# 2_MCU_schdoc.net
KiCad netlist of a schematic drawn in Altium Designer
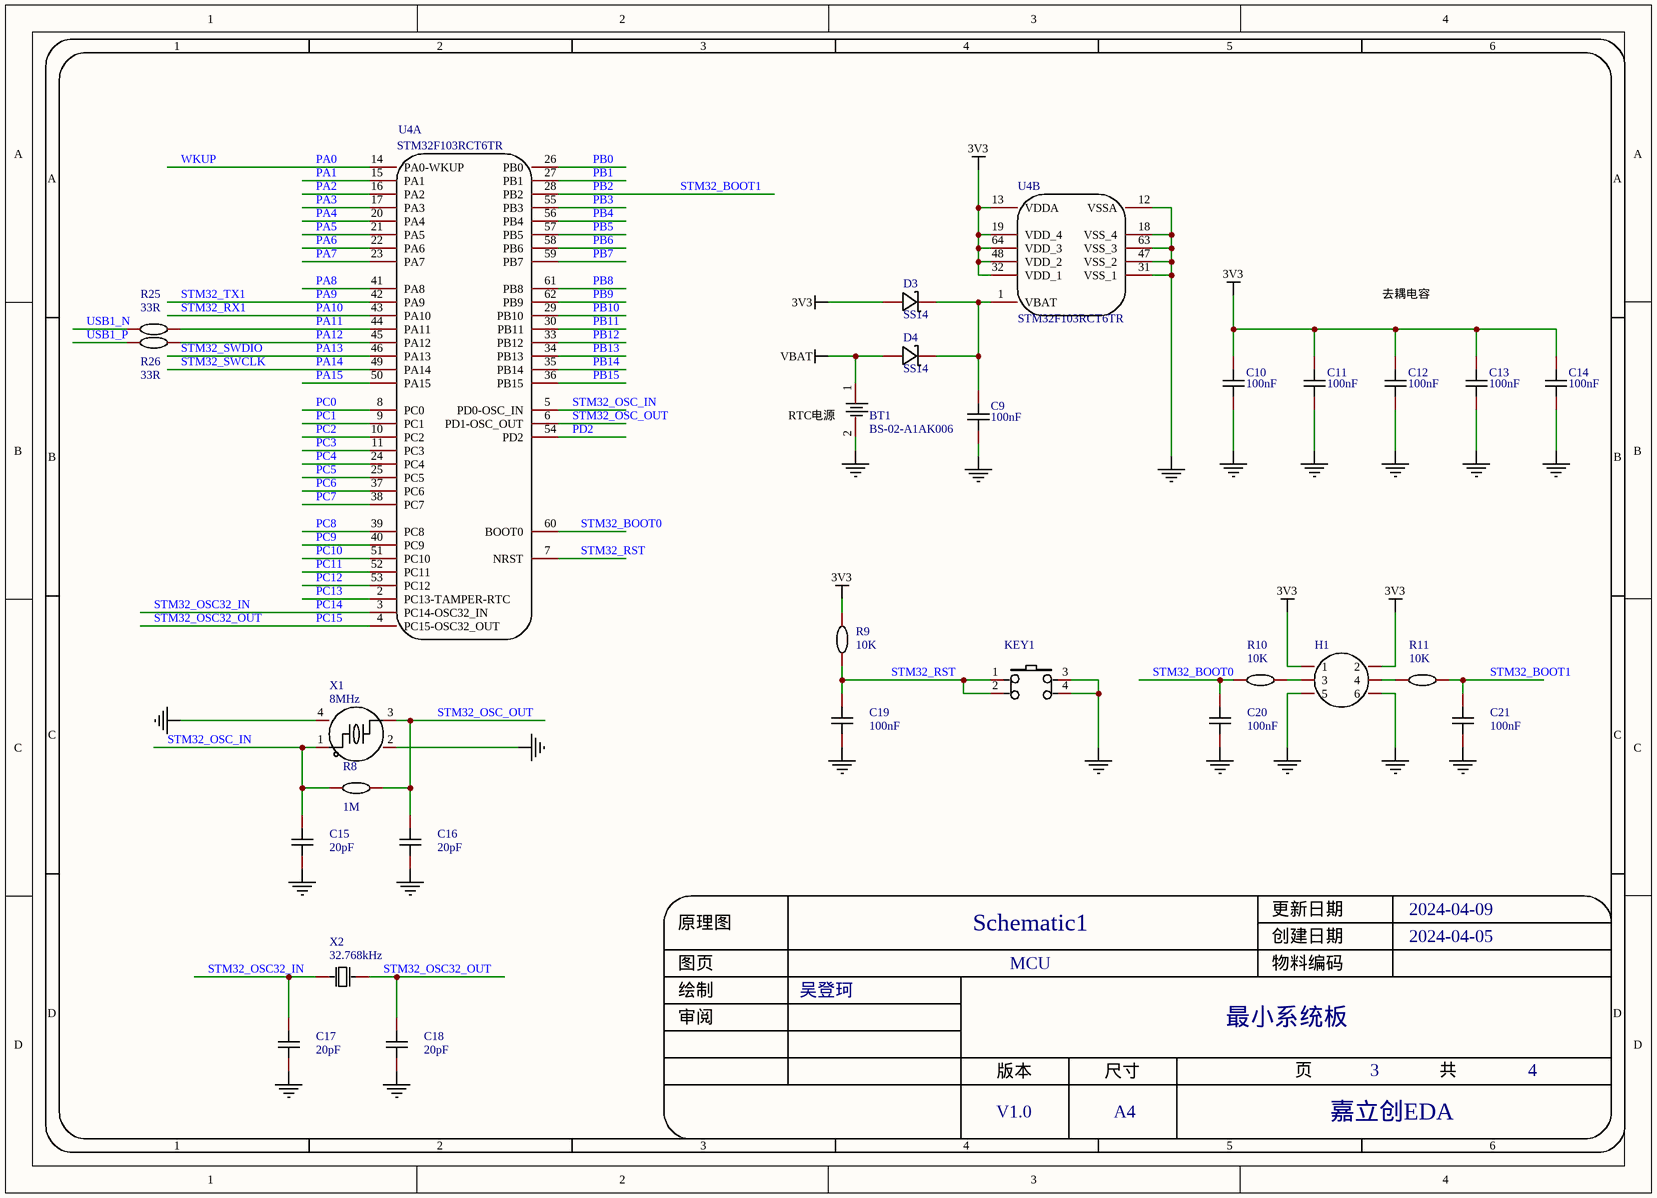
[diagram p0: 2_MCU.schdoc.schdoc]

(export (version "E")
  (design (tool "Eeschema 10.0.6"))
  (components
    (comp (ref "BT1")
      (value "BS-02-A1AK006")
      (footprint "BAT-TH_BS-02-A1AK006")
      (fields (field (name "NAME") "BS-02-A1AK006") (field (name "MANUFACTURER") "MYOUNG(美阳)"))
      (libsource (lib "altium-import") (part "root_3_BS-02-A1AK006_"))
    )
    (comp (ref "C9")
      (value "100nF")
      (footprint "C0603")
      (fields (field (name "NAME") "100nF"))
      (libsource (lib "altium-import") (part "root_1_CAP_0603_"))
    )
    (comp (ref "C10")
      (value "100nF")
      (footprint "C0603")
      (fields (field (name "NAME") "100nF"))
      (libsource (lib "altium-import") (part "root_1_CAP_0603_"))
    )
    (comp (ref "C11")
      (value "100nF")
      (footprint "C0603")
      (fields (field (name "NAME") "100nF"))
      (libsource (lib "altium-import") (part "root_1_CAP_0603_"))
    )
    (comp (ref "C12")
      (value "100nF")
      (footprint "C0603")
      (fields (field (name "NAME") "100nF"))
      (libsource (lib "altium-import") (part "root_1_CAP_0603_"))
    )
    (comp (ref "C13")
      (value "100nF")
      (footprint "C0603")
      (fields (field (name "NAME") "100nF"))
      (libsource (lib "altium-import") (part "root_1_CAP_0603_"))
    )
    (comp (ref "C14")
      (value "100nF")
      (footprint "C0603")
      (fields (field (name "NAME") "100nF"))
      (libsource (lib "altium-import") (part "root_1_CAP_0603_"))
    )
    (comp (ref "C15")
      (value "20pF")
      (footprint "C0603")
      (fields (field (name "NAME") "20pF"))
      (libsource (lib "altium-import") (part "root_1_CAP_0603_"))
    )
    (comp (ref "C16")
      (value "20pF")
      (footprint "C0603")
      (fields (field (name "NAME") "20pF"))
      (libsource (lib "altium-import") (part "root_1_CAP_0603_"))
    )
    (comp (ref "C17")
      (value "20pF")
      (footprint "C0603")
      (fields (field (name "NAME") "20pF"))
      (libsource (lib "altium-import") (part "root_1_CAP_0603_"))
    )
    (comp (ref "C18")
      (value "20pF")
      (footprint "C0603")
      (fields (field (name "NAME") "20pF"))
      (libsource (lib "altium-import") (part "root_1_CAP_0603_"))
    )
    (comp (ref "C19")
      (value "100nF")
      (footprint "C0603")
      (fields (field (name "NAME") "100nF"))
      (libsource (lib "altium-import") (part "root_1_CAP_0603_"))
    )
    (comp (ref "C20")
      (value "100nF")
      (footprint "C0603")
      (fields (field (name "NAME") "100nF"))
      (libsource (lib "altium-import") (part "root_1_CAP_0603_"))
    )
    (comp (ref "C21")
      (value "100nF")
      (footprint "C0603")
      (fields (field (name "NAME") "100nF"))
      (libsource (lib "altium-import") (part "root_1_CAP_0603_"))
    )
    (comp (ref "D3")
      (value "SS14")
      (footprint "SMA_L4.3-W2.6-LS5.2-RD")
      (fields (field (name "NAME") "SS14") (field (name "MANUFACTURER") "onsemi(安森美)"))
      (libsource (lib "altium-import") (part "root_2_SS14_C83852_"))
    )
    (comp (ref "D4")
      (value "SS14")
      (footprint "SMA_L4.3-W2.6-LS5.2-RD")
      (fields (field (name "NAME") "SS14") (field (name "MANUFACTURER") "onsemi(安森美)"))
      (libsource (lib "altium-import") (part "root_2_SS14_C83852_"))
    )
    (comp (ref "H1")
      (value "HDR-F_2.54_2x3")
      (footprint "HDR-TH_6P-P2.54-V-F-R2-C3-S2.54")
      (libsource (lib "altium-import") (part "root_0_HDR-F_2.54_2x3_"))
    )
    (comp (ref "KEY1")
      (value "6x6x6塑料头")
      (footprint "SW-SMD_4P-L6.0-W6.0-P4.50-LS8.6")
      (fields (field (name "MANUFACTURER") "国产"))
      (libsource (lib "altium-import") (part "root_0_6x6x6塑料头_"))
    )
    (comp (ref "R8")
      (value "1M")
      (footprint "R0603")
      (fields (field (name "NAME") "1M"))
      (libsource (lib "altium-import") (part "root_0_Res_0603_"))
    )
    (comp (ref "R9")
      (value "10K")
      (footprint "R0603")
      (fields (field (name "NAME") "10K"))
      (libsource (lib "altium-import") (part "root_1_Res_0603_"))
    )
    (comp (ref "R10")
      (value "10K")
      (footprint "R0603")
      (fields (field (name "NAME") "10K"))
      (libsource (lib "altium-import") (part "root_0_Res_0603_"))
    )
    (comp (ref "R11")
      (value "10K")
      (footprint "R0603")
      (fields (field (name "NAME") "10K"))
      (libsource (lib "altium-import") (part "root_0_Res_0603_"))
    )
    (comp (ref "R25")
      (value "33R")
      (footprint "R0603")
      (fields (field (name "NAME") "33R"))
      (libsource (lib "altium-import") (part "root_0_Res_0603_"))
    )
    (comp (ref "R26")
      (value "33R")
      (footprint "R0603")
      (fields (field (name "NAME") "33R"))
      (libsource (lib "altium-import") (part "root_0_Res_0603_"))
    )
    (comp (ref "U4")
      (value "STM32F103RCT6TR")
      (footprint "LQFP-64_L10.0-W10.0-P0.50-LS12.0-BL")
      (fields (field (name "NAME") "STM32F103RCT6TR") (field (name "MANUFACTURER") "ST(意法半导体)"))
      (libsource (lib "altium-import") (part "root_0_STM32F103RCT6TR_"))
    )
    (comp (ref "X1")
      (value "8MHz")
      (footprint "OSC-SMD_4P-L3.2-W2.5-BL")
      (fields
        (field (name "NAME") "8MHz")
        (field (name "MANUFACTURER") "YXC(扬兴晶振)")
        (field (name "MANUFACTURER PART") "X32258MOB4SI")
      )
      (libsource (lib "altium-import") (part "root_0_X32258MOB4SI_"))
    )
    (comp (ref "X2")
      (value "32.768kHz")
      (footprint "OSC-SMD_L3.2-W1.5")
      (fields
        (field (name "NAME") "32.768kHz")
        (field (name "MANUFACTURER") "KDS(大真空)")
        (field (name "MANUFACTURER PART") "DST310S 32.768KHz")
      )
      (libsource (lib "altium-import") (part "root_0_DST310S 32.768KHz_"))
    )
  )
  (nets
    (net (code "1") (name "/PA0") (class "Default")
      (node (ref "U4") (pin "14") (pinfunction "PA0-WKUP_14") (pintype "passive"))
    )
    (net (code "2") (name "/PA1") (class "Default")
      (node (ref "U4") (pin "15") (pinfunction "PA1_15") (pintype "passive"))
    )
    (net (code "3") (name "/PA2") (class "Default")
      (node (ref "U4") (pin "16") (pinfunction "PA2_16") (pintype "passive"))
    )
    (net (code "4") (name "/PA3") (class "Default")
      (node (ref "U4") (pin "17") (pinfunction "PA3_17") (pintype "passive"))
    )
    (net (code "5") (name "/PA4") (class "Default")
      (node (ref "U4") (pin "20") (pinfunction "PA4_20") (pintype "passive"))
    )
    (net (code "6") (name "/PA5") (class "Default")
      (node (ref "U4") (pin "21") (pinfunction "PA5_21") (pintype "passive"))
    )
    (net (code "7") (name "/PA6") (class "Default")
      (node (ref "U4") (pin "22") (pinfunction "PA6_22") (pintype "passive"))
    )
    (net (code "8") (name "/PA7") (class "Default")
      (node (ref "U4") (pin "23") (pinfunction "PA7_23") (pintype "passive"))
    )
    (net (code "9") (name "/PA8") (class "Default")
      (node (ref "U4") (pin "41") (pinfunction "PA8_41") (pintype "passive"))
    )
    (net (code "10") (name "/PA9") (class "Default")
      (node (ref "U4") (pin "42") (pinfunction "PA9_42") (pintype "passive"))
    )
    (net (code "11") (name "/PA10") (class "Default")
      (node (ref "U4") (pin "43") (pinfunction "PA10_43") (pintype "passive"))
    )
    (net (code "12") (name "/PA11") (class "Default")
      (node (ref "R25") (pin "2") (pinfunction "2_2") (pintype "passive"))
      (node (ref "U4") (pin "44") (pinfunction "PA11_44") (pintype "passive"))
    )
    (net (code "13") (name "/PA12") (class "Default")
      (node (ref "R26") (pin "2") (pinfunction "2_2") (pintype "passive"))
      (node (ref "U4") (pin "45") (pinfunction "PA12_45") (pintype "passive"))
    )
    (net (code "14") (name "/PA13") (class "Default")
      (node (ref "U4") (pin "46") (pinfunction "PA13_46") (pintype "passive"))
    )
    (net (code "15") (name "/PA14") (class "Default")
      (node (ref "U4") (pin "49") (pinfunction "PA14_49") (pintype "passive"))
    )
    (net (code "16") (name "/PA15") (class "Default")
      (node (ref "U4") (pin "50") (pinfunction "PA15_50") (pintype "passive"))
    )
    (net (code "17") (name "/PB0") (class "Default")
      (node (ref "U4") (pin "26") (pinfunction "PB0_26") (pintype "passive"))
    )
    (net (code "18") (name "/PB1") (class "Default")
      (node (ref "U4") (pin "27") (pinfunction "PB1_27") (pintype "passive"))
    )
    (net (code "19") (name "/PB2") (class "Default")
      (node (ref "C21") (pin "2") (pinfunction "2_2") (pintype "passive"))
      (node (ref "R11") (pin "2") (pinfunction "2_2") (pintype "passive"))
      (node (ref "U4") (pin "28") (pinfunction "PB2_28") (pintype "passive"))
    )
    (net (code "20") (name "/PB3") (class "Default")
      (node (ref "U4") (pin "55") (pinfunction "PB3_55") (pintype "passive"))
    )
    (net (code "21") (name "/PB4") (class "Default")
      (node (ref "U4") (pin "56") (pinfunction "PB4_56") (pintype "passive"))
    )
    (net (code "22") (name "/PB5") (class "Default")
      (node (ref "U4") (pin "57") (pinfunction "PB5_57") (pintype "passive"))
    )
    (net (code "23") (name "/PB6") (class "Default")
      (node (ref "U4") (pin "58") (pinfunction "PB6_58") (pintype "passive"))
    )
    (net (code "24") (name "/PB7") (class "Default")
      (node (ref "U4") (pin "59") (pinfunction "PB7_59") (pintype "passive"))
    )
    (net (code "25") (name "/PB8") (class "Default")
      (node (ref "U4") (pin "61") (pinfunction "PB8_61") (pintype "passive"))
    )
    (net (code "26") (name "/PB9") (class "Default")
      (node (ref "U4") (pin "62") (pinfunction "PB9_62") (pintype "passive"))
    )
    (net (code "27") (name "/PB10") (class "Default")
      (node (ref "U4") (pin "29") (pinfunction "PB10_29") (pintype "passive"))
    )
    (net (code "28") (name "/PB11") (class "Default")
      (node (ref "U4") (pin "30") (pinfunction "PB11_30") (pintype "passive"))
    )
    (net (code "29") (name "/PB12") (class "Default")
      (node (ref "U4") (pin "33") (pinfunction "PB12_33") (pintype "passive"))
    )
    (net (code "30") (name "/PB13") (class "Default")
      (node (ref "U4") (pin "34") (pinfunction "PB13_34") (pintype "passive"))
    )
    (net (code "31") (name "/PB14") (class "Default")
      (node (ref "U4") (pin "35") (pinfunction "PB14_35") (pintype "passive"))
    )
    (net (code "32") (name "/PB15") (class "Default")
      (node (ref "U4") (pin "36") (pinfunction "PB15_36") (pintype "passive"))
    )
    (net (code "33") (name "/PC0") (class "Default")
      (node (ref "U4") (pin "8") (pinfunction "PC0_8") (pintype "passive"))
    )
    (net (code "34") (name "/PC1") (class "Default")
      (node (ref "U4") (pin "9") (pinfunction "PC1_9") (pintype "passive"))
    )
    (net (code "35") (name "/PC2") (class "Default")
      (node (ref "U4") (pin "10") (pinfunction "PC2_10") (pintype "passive"))
    )
    (net (code "36") (name "/PC3") (class "Default")
      (node (ref "U4") (pin "11") (pinfunction "PC3_11") (pintype "passive"))
    )
    (net (code "37") (name "/PC4") (class "Default")
      (node (ref "U4") (pin "24") (pinfunction "PC4_24") (pintype "passive"))
    )
    (net (code "38") (name "/PC5") (class "Default")
      (node (ref "U4") (pin "25") (pinfunction "PC5_25") (pintype "passive"))
    )
    (net (code "39") (name "/PC6") (class "Default")
      (node (ref "U4") (pin "37") (pinfunction "PC6_37") (pintype "passive"))
    )
    (net (code "40") (name "/PC7") (class "Default")
      (node (ref "U4") (pin "38") (pinfunction "PC7_38") (pintype "passive"))
    )
    (net (code "41") (name "/PC8") (class "Default")
      (node (ref "U4") (pin "39") (pinfunction "PC8_39") (pintype "passive"))
    )
    (net (code "42") (name "/PC9") (class "Default")
      (node (ref "U4") (pin "40") (pinfunction "PC9_40") (pintype "passive"))
    )
    (net (code "43") (name "/PC10") (class "Default")
      (node (ref "U4") (pin "51") (pinfunction "PC10_51") (pintype "passive"))
    )
    (net (code "44") (name "/PC11") (class "Default")
      (node (ref "U4") (pin "52") (pinfunction "PC11_52") (pintype "passive"))
    )
    (net (code "45") (name "/PC12") (class "Default")
      (node (ref "U4") (pin "53") (pinfunction "PC12_53") (pintype "passive"))
    )
    (net (code "46") (name "/PC13") (class "Default")
      (node (ref "U4") (pin "2") (pinfunction "PC13-TAMPER-RTC_2") (pintype "passive"))
    )
    (net (code "47") (name "/PC14") (class "Default")
      (node (ref "C17") (pin "2") (pinfunction "2_2") (pintype "passive"))
      (node (ref "U4") (pin "3") (pinfunction "PC14-OSC32_IN_3") (pintype "passive"))
      (node (ref "X2") (pin "1") (pinfunction "OSC1_1") (pintype "passive"))
    )
    (net (code "48") (name "/PC15") (class "Default")
      (node (ref "C18") (pin "2") (pinfunction "2_2") (pintype "passive"))
      (node (ref "U4") (pin "4") (pinfunction "PC15-OSC32_OUT_4") (pintype "passive"))
      (node (ref "X2") (pin "2") (pinfunction "OSC2_2") (pintype "passive"))
    )
    (net (code "49") (name "/PD2") (class "Default")
      (node (ref "U4") (pin "54") (pinfunction "PD2_54") (pintype "passive"))
    )
    (net (code "50") (name "/STM32_BOOT0") (class "Default")
      (node (ref "C20") (pin "2") (pinfunction "2_2") (pintype "passive"))
      (node (ref "R10") (pin "1") (pinfunction "1_1") (pintype "passive"))
      (node (ref "U4") (pin "60") (pinfunction "BOOT0_60") (pintype "passive"))
    )
    (net (code "51") (name "/STM32_OSC_IN") (class "Default")
      (node (ref "C15") (pin "2") (pinfunction "2_2") (pintype "passive"))
      (node (ref "R8") (pin "1") (pinfunction "1_1") (pintype "passive"))
      (node (ref "U4") (pin "5") (pinfunction "PD0-OSC_IN_5") (pintype "passive"))
      (node (ref "X1") (pin "1") (pinfunction "1_1") (pintype "passive"))
    )
    (net (code "52") (name "/STM32_OSC_OUT") (class "Default")
      (node (ref "C16") (pin "2") (pinfunction "2_2") (pintype "passive"))
      (node (ref "R8") (pin "2") (pinfunction "2_2") (pintype "passive"))
      (node (ref "U4") (pin "6") (pinfunction "PD1-OSC_OUT_6") (pintype "passive"))
      (node (ref "X1") (pin "3") (pinfunction "3_3") (pintype "passive"))
    )
    (net (code "53") (name "/STM32_RST") (class "Default")
      (node (ref "C19") (pin "2") (pinfunction "2_2") (pintype "passive"))
      (node (ref "KEY1") (pin "1") (pinfunction "1_1") (pintype "passive"))
      (node (ref "KEY1") (pin "2") (pinfunction "2_2") (pintype "passive"))
      (node (ref "R9") (pin "1") (pinfunction "1_1") (pintype "passive"))
      (node (ref "U4") (pin "7") (pinfunction "NRST_7") (pintype "passive"))
    )
    (net (code "54") (name "/USB1_N") (class "Default")
      (node (ref "R25") (pin "1") (pinfunction "1_1") (pintype "passive"))
    )
    (net (code "55") (name "/USB1_P") (class "Default")
      (node (ref "R26") (pin "1") (pinfunction "1_1") (pintype "passive"))
    )
    (net (code "56") (name "3V3") (class "Default")
      (node (ref "C10") (pin "2") (pinfunction "2_2") (pintype "passive"))
      (node (ref "C11") (pin "2") (pinfunction "2_2") (pintype "passive"))
      (node (ref "C12") (pin "2") (pinfunction "2_2") (pintype "passive"))
      (node (ref "C13") (pin "2") (pinfunction "2_2") (pintype "passive"))
      (node (ref "C14") (pin "2") (pinfunction "2_2") (pintype "passive"))
      (node (ref "D3") (pin "2") (pinfunction "A_2") (pintype "passive"))
      (node (ref "H1") (pin "1") (pinfunction "1_1") (pintype "passive"))
      (node (ref "H1") (pin "2") (pinfunction "2_2") (pintype "passive"))
      (node (ref "R9") (pin "2") (pinfunction "2_2") (pintype "passive"))
      (node (ref "U4") (pin "13") (pinfunction "VDDA_13") (pintype "passive"))
      (node (ref "U4") (pin "19") (pinfunction "VDD_4_19") (pintype "passive"))
      (node (ref "U4") (pin "32") (pinfunction "VDD_1_32") (pintype "passive"))
      (node (ref "U4") (pin "48") (pinfunction "VDD_2_48") (pintype "passive"))
      (node (ref "U4") (pin "64") (pinfunction "VDD_3_64") (pintype "passive"))
    )
    (net (code "57") (name "<NO NET>") (class "Default")
      (node (ref "BT1") (pin "2") (pinfunction "2_2") (pintype "passive"))
      (node (ref "C10") (pin "1") (pinfunction "1_1") (pintype "passive"))
      (node (ref "C11") (pin "1") (pinfunction "1_1") (pintype "passive"))
      (node (ref "C12") (pin "1") (pinfunction "1_1") (pintype "passive"))
      (node (ref "C13") (pin "1") (pinfunction "1_1") (pintype "passive"))
      (node (ref "C14") (pin "1") (pinfunction "1_1") (pintype "passive"))
      (node (ref "C15") (pin "1") (pinfunction "1_1") (pintype "passive"))
      (node (ref "C16") (pin "1") (pinfunction "1_1") (pintype "passive"))
      (node (ref "C17") (pin "1") (pinfunction "1_1") (pintype "passive"))
      (node (ref "C18") (pin "1") (pinfunction "1_1") (pintype "passive"))
      (node (ref "C19") (pin "1") (pinfunction "1_1") (pintype "passive"))
      (node (ref "C20") (pin "1") (pinfunction "1_1") (pintype "passive"))
      (node (ref "C21") (pin "1") (pinfunction "1_1") (pintype "passive"))
      (node (ref "C9") (pin "1") (pinfunction "1_1") (pintype "passive"))
      (node (ref "H1") (pin "5") (pinfunction "5_5") (pintype "passive"))
      (node (ref "H1") (pin "6") (pinfunction "6_6") (pintype "passive"))
      (node (ref "KEY1") (pin "3") (pinfunction "3_3") (pintype "passive"))
      (node (ref "KEY1") (pin "4") (pinfunction "4_4") (pintype "passive"))
      (node (ref "U4") (pin "12") (pinfunction "VSSA_12") (pintype "passive"))
      (node (ref "U4") (pin "18") (pinfunction "VSS_4_18") (pintype "passive"))
      (node (ref "U4") (pin "31") (pinfunction "VSS_1_31") (pintype "passive"))
      (node (ref "U4") (pin "47") (pinfunction "VSS_2_47") (pintype "passive"))
      (node (ref "U4") (pin "63") (pinfunction "VSS_3_63") (pintype "passive"))
      (node (ref "X1") (pin "2") (pinfunction "GND_2") (pintype "passive"))
      (node (ref "X1") (pin "4") (pinfunction "GND_4") (pintype "passive"))
    )
    (net (code "58") (name "Net-(D3-K)") (class "Default")
      (node (ref "C9") (pin "2") (pinfunction "2_2") (pintype "passive"))
      (node (ref "D3") (pin "1") (pinfunction "K_1") (pintype "passive"))
      (node (ref "D4") (pin "1") (pinfunction "K_1") (pintype "passive"))
      (node (ref "U4") (pin "1") (pinfunction "VBAT_1") (pintype "passive"))
    )
    (net (code "59") (name "Net-(H1-Pad3)") (class "Default")
      (node (ref "H1") (pin "3") (pinfunction "3_3") (pintype "passive"))
      (node (ref "R10") (pin "2") (pinfunction "2_2") (pintype "passive"))
    )
    (net (code "60") (name "Net-(H1-Pad4)") (class "Default")
      (node (ref "H1") (pin "4") (pinfunction "4_4") (pintype "passive"))
      (node (ref "R11") (pin "1") (pinfunction "1_1") (pintype "passive"))
    )
    (net (code "61") (name "VBAT") (class "Default")
      (node (ref "BT1") (pin "1") (pinfunction "1_1") (pintype "passive"))
      (node (ref "D4") (pin "2") (pinfunction "A_2") (pintype "passive"))
    )
  )
)
